# phy0.net
KiCad netlist of a schematic drawn in Altium Designer
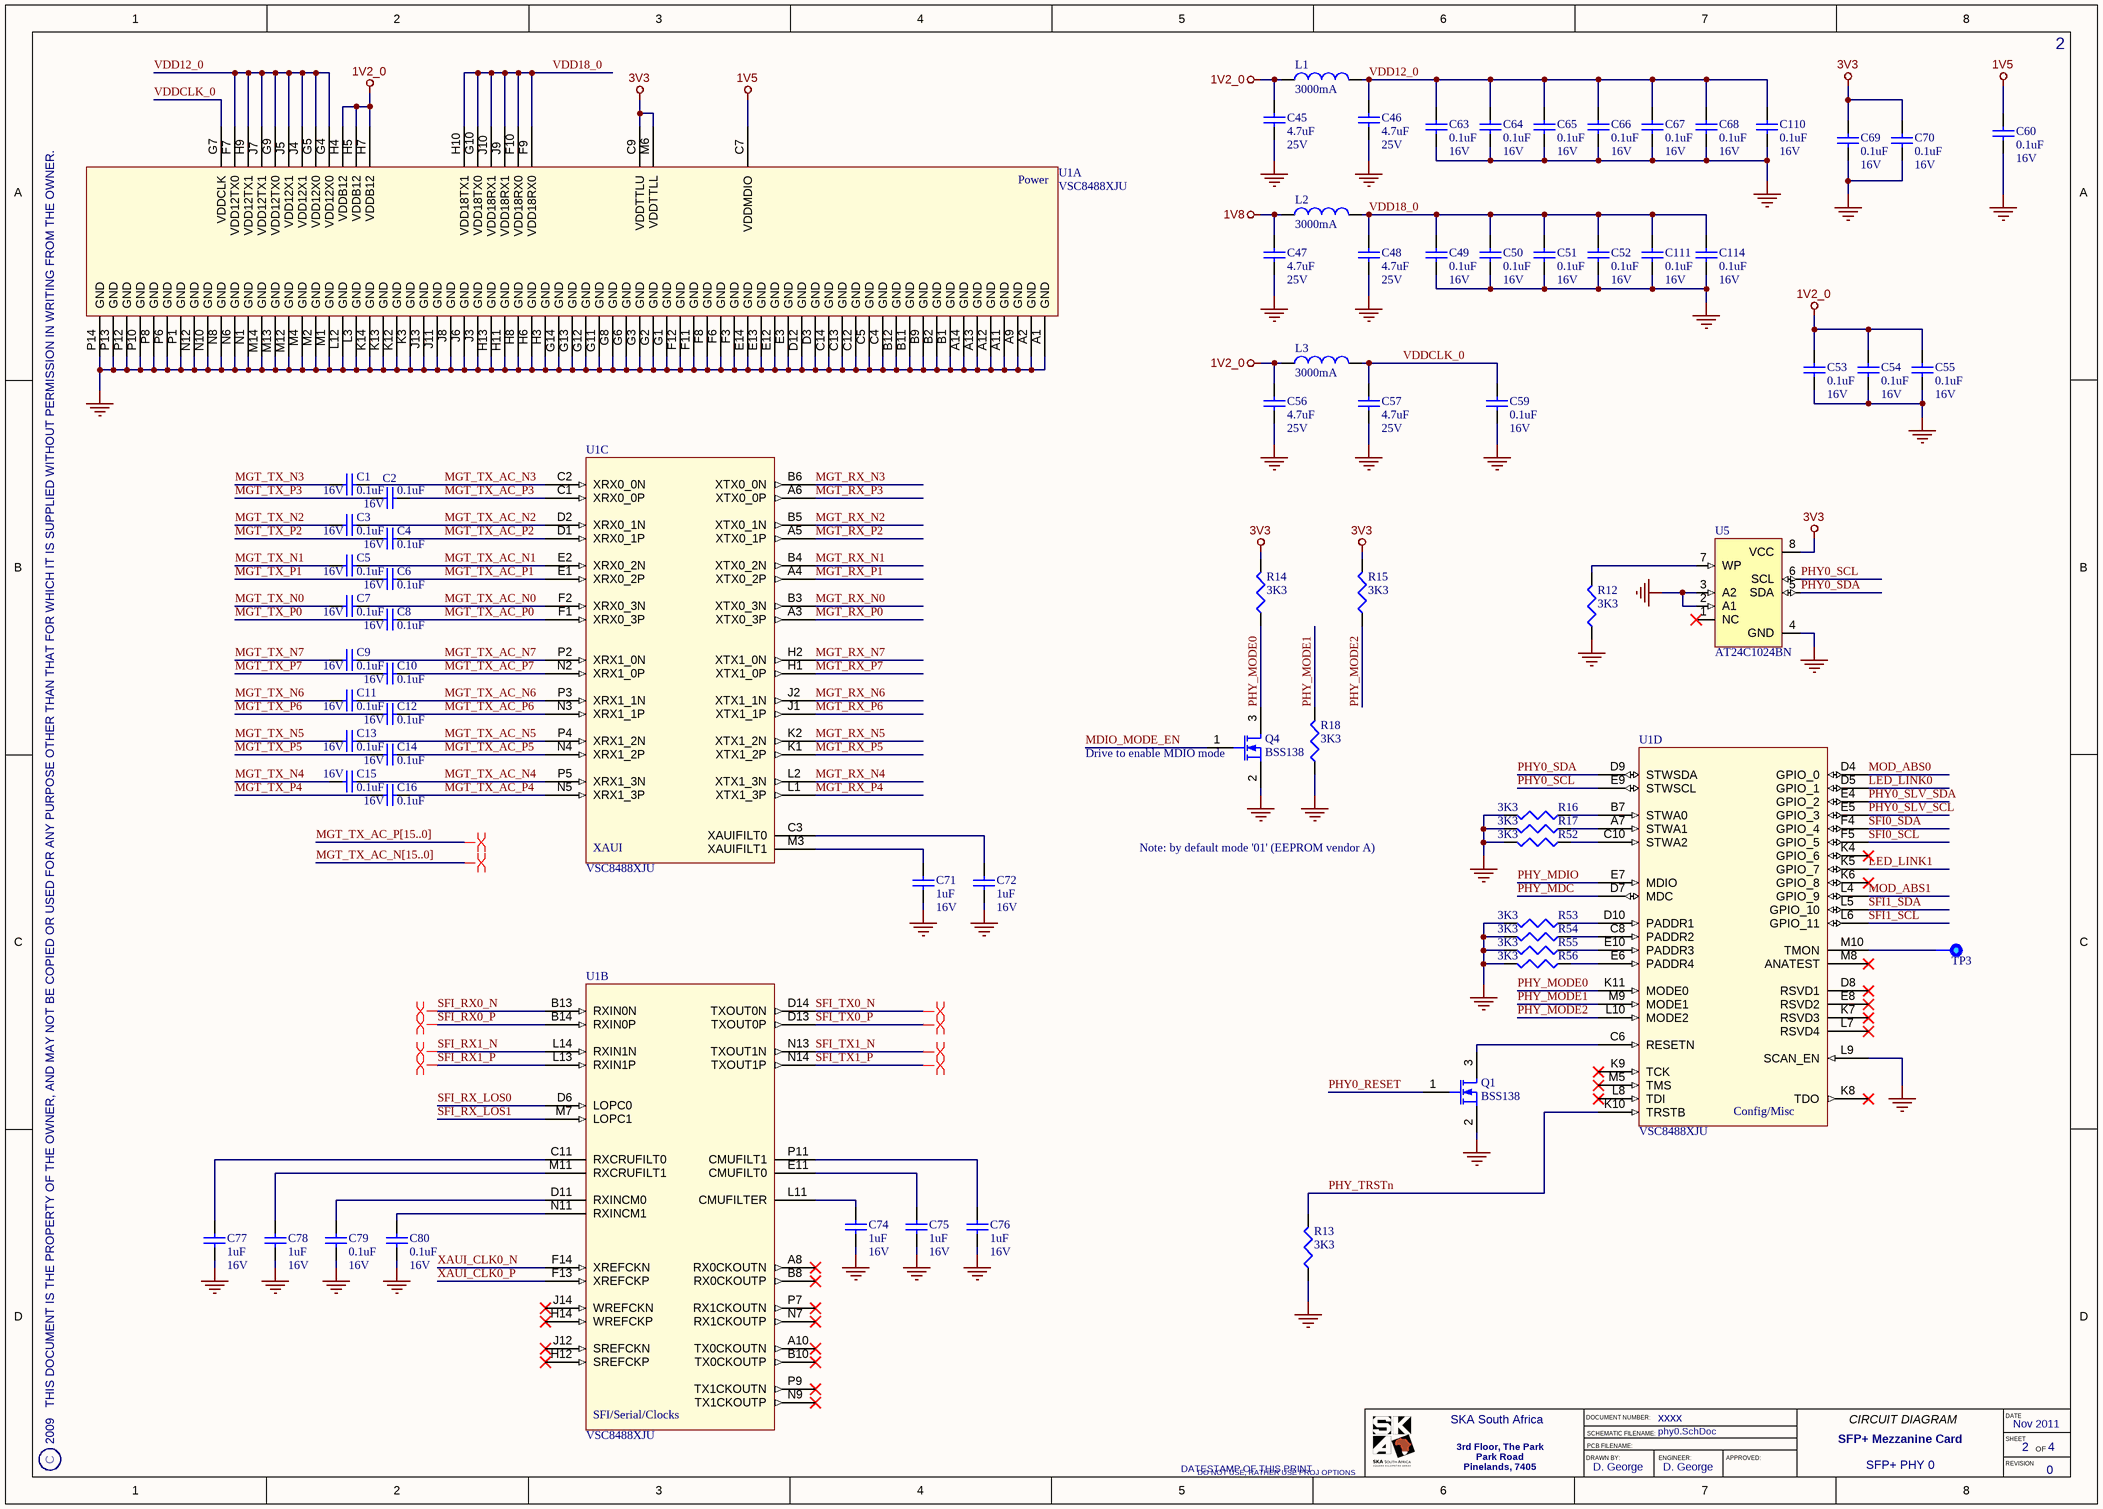
[diagram p0: phy0.SchDoc]

(export (version "E")
  (design (tool "Eeschema 10.0.6"))
  (components
    (comp (ref "C1")
      (value "0.1uF")
      (footprint "CAPC1005X60L")
      (description "0.1uF, Ceramic Capacitor")
      (fields
        (field (name "RATING") "16V")
        (field (name "MANUFACTURER") "VENKEL")
        (field (name "PARTNUM") "C0402X7R160-104KN")
      )
      (libsource (lib "altium_db") (part "CapStd"))
    )
    (comp (ref "C2")
      (value "0.1uF")
      (footprint "CAPC1005X60L")
      (description "0.1uF, Ceramic Capacitor")
      (fields
        (field (name "RATING") "16V")
        (field (name "MANUFACTURER") "VENKEL")
        (field (name "PARTNUM") "C0402X7R160-104KN")
      )
      (libsource (lib "altium_db") (part "CapStd"))
    )
    (comp (ref "C3")
      (value "0.1uF")
      (footprint "CAPC1005X60L")
      (description "0.1uF, Ceramic Capacitor")
      (fields
        (field (name "RATING") "16V")
        (field (name "MANUFACTURER") "VENKEL")
        (field (name "PARTNUM") "C0402X7R160-104KN")
      )
      (libsource (lib "altium_db") (part "CapStd"))
    )
    (comp (ref "C4")
      (value "0.1uF")
      (footprint "CAPC1005X60L")
      (description "0.1uF, Ceramic Capacitor")
      (fields
        (field (name "RATING") "16V")
        (field (name "MANUFACTURER") "VENKEL")
        (field (name "PARTNUM") "C0402X7R160-104KN")
      )
      (libsource (lib "altium_db") (part "CapStd"))
    )
    (comp (ref "C5")
      (value "0.1uF")
      (footprint "CAPC1005X60L")
      (description "0.1uF, Ceramic Capacitor")
      (fields
        (field (name "RATING") "16V")
        (field (name "MANUFACTURER") "VENKEL")
        (field (name "PARTNUM") "C0402X7R160-104KN")
      )
      (libsource (lib "altium_db") (part "CapStd"))
    )
    (comp (ref "C6")
      (value "0.1uF")
      (footprint "CAPC1005X60L")
      (description "0.1uF, Ceramic Capacitor")
      (fields
        (field (name "RATING") "16V")
        (field (name "MANUFACTURER") "VENKEL")
        (field (name "PARTNUM") "C0402X7R160-104KN")
      )
      (libsource (lib "altium_db") (part "CapStd"))
    )
    (comp (ref "C7")
      (value "0.1uF")
      (footprint "CAPC1005X60L")
      (description "0.1uF, Ceramic Capacitor")
      (fields
        (field (name "RATING") "16V")
        (field (name "MANUFACTURER") "VENKEL")
        (field (name "PARTNUM") "C0402X7R160-104KN")
      )
      (libsource (lib "altium_db") (part "CapStd"))
    )
    (comp (ref "C8")
      (value "0.1uF")
      (footprint "CAPC1005X60L")
      (description "0.1uF, Ceramic Capacitor")
      (fields
        (field (name "RATING") "16V")
        (field (name "MANUFACTURER") "VENKEL")
        (field (name "PARTNUM") "C0402X7R160-104KN")
      )
      (libsource (lib "altium_db") (part "CapStd"))
    )
    (comp (ref "C9")
      (value "0.1uF")
      (footprint "CAPC1005X60L")
      (description "0.1uF, Ceramic Capacitor")
      (fields
        (field (name "RATING") "16V")
        (field (name "MANUFACTURER") "VENKEL")
        (field (name "PARTNUM") "C0402X7R160-104KN")
      )
      (libsource (lib "altium_db") (part "CapStd"))
    )
    (comp (ref "C10")
      (value "0.1uF")
      (footprint "CAPC1005X60L")
      (description "0.1uF, Ceramic Capacitor")
      (fields
        (field (name "RATING") "16V")
        (field (name "MANUFACTURER") "VENKEL")
        (field (name "PARTNUM") "C0402X7R160-104KN")
      )
      (libsource (lib "altium_db") (part "CapStd"))
    )
    (comp (ref "C11")
      (value "0.1uF")
      (footprint "CAPC1005X60L")
      (description "0.1uF, Ceramic Capacitor")
      (fields
        (field (name "RATING") "16V")
        (field (name "MANUFACTURER") "VENKEL")
        (field (name "PARTNUM") "C0402X7R160-104KN")
      )
      (libsource (lib "altium_db") (part "CapStd"))
    )
    (comp (ref "C12")
      (value "0.1uF")
      (footprint "CAPC1005X60L")
      (description "0.1uF, Ceramic Capacitor")
      (fields
        (field (name "RATING") "16V")
        (field (name "MANUFACTURER") "VENKEL")
        (field (name "PARTNUM") "C0402X7R160-104KN")
      )
      (libsource (lib "altium_db") (part "CapStd"))
    )
    (comp (ref "C13")
      (value "0.1uF")
      (footprint "CAPC1005X60L")
      (description "0.1uF, Ceramic Capacitor")
      (fields
        (field (name "RATING") "16V")
        (field (name "MANUFACTURER") "VENKEL")
        (field (name "PARTNUM") "C0402X7R160-104KN")
      )
      (libsource (lib "altium_db") (part "CapStd"))
    )
    (comp (ref "C14")
      (value "0.1uF")
      (footprint "CAPC1005X60L")
      (description "0.1uF, Ceramic Capacitor")
      (fields
        (field (name "RATING") "16V")
        (field (name "MANUFACTURER") "VENKEL")
        (field (name "PARTNUM") "C0402X7R160-104KN")
      )
      (libsource (lib "altium_db") (part "CapStd"))
    )
    (comp (ref "C15")
      (value "0.1uF")
      (footprint "CAPC1005X60L")
      (description "0.1uF, Ceramic Capacitor")
      (fields
        (field (name "RATING") "16V")
        (field (name "MANUFACTURER") "VENKEL")
        (field (name "PARTNUM") "C0402X7R160-104KN")
      )
      (libsource (lib "altium_db") (part "CapStd"))
    )
    (comp (ref "C16")
      (value "0.1uF")
      (footprint "CAPC1005X60L")
      (description "0.1uF, Ceramic Capacitor")
      (fields
        (field (name "RATING") "16V")
        (field (name "MANUFACTURER") "VENKEL")
        (field (name "PARTNUM") "C0402X7R160-104KN")
      )
      (libsource (lib "altium_db") (part "CapStd"))
    )
    (comp (ref "C45")
      (value "4.7uF")
      (footprint "CAPC2012X127L")
      (description "4.7uF, Ceramic Capacitor")
      (fields
        (field (name "RATING") "25V")
        (field (name "MANUFACTURER") "MURATA")
        (field (name "PARTNUM") "GRM21BR61E475KA12K")
      )
      (libsource (lib "altium_db") (part "CapStd"))
    )
    (comp (ref "C46")
      (value "4.7uF")
      (footprint "CAPC2012X127L")
      (description "4.7uF, Ceramic Capacitor")
      (fields
        (field (name "RATING") "25V")
        (field (name "MANUFACTURER") "MURATA")
        (field (name "PARTNUM") "GRM21BR61E475KA12K")
      )
      (libsource (lib "altium_db") (part "CapStd"))
    )
    (comp (ref "C47")
      (value "4.7uF")
      (footprint "CAPC2012X127L")
      (description "4.7uF, Ceramic Capacitor")
      (fields
        (field (name "RATING") "25V")
        (field (name "MANUFACTURER") "MURATA")
        (field (name "PARTNUM") "GRM21BR61E475KA12K")
      )
      (libsource (lib "altium_db") (part "CapStd"))
    )
    (comp (ref "C48")
      (value "4.7uF")
      (footprint "CAPC2012X127L")
      (description "4.7uF, Ceramic Capacitor")
      (fields
        (field (name "RATING") "25V")
        (field (name "MANUFACTURER") "MURATA")
        (field (name "PARTNUM") "GRM21BR61E475KA12K")
      )
      (libsource (lib "altium_db") (part "CapStd"))
    )
    (comp (ref "C49")
      (value "0.1uF")
      (footprint "CAPC1005X60L")
      (description "0.1uF, Ceramic Capacitor")
      (fields
        (field (name "RATING") "16V")
        (field (name "MANUFACTURER") "VENKEL")
        (field (name "PARTNUM") "C0402X7R160-104KN")
      )
      (libsource (lib "altium_db") (part "CapStd"))
    )
    (comp (ref "C50")
      (value "0.1uF")
      (footprint "CAPC1005X60L")
      (description "0.1uF, Ceramic Capacitor")
      (fields
        (field (name "RATING") "16V")
        (field (name "MANUFACTURER") "VENKEL")
        (field (name "PARTNUM") "C0402X7R160-104KN")
      )
      (libsource (lib "altium_db") (part "CapStd"))
    )
    (comp (ref "C51")
      (value "0.1uF")
      (footprint "CAPC1005X60L")
      (description "0.1uF, Ceramic Capacitor")
      (fields
        (field (name "RATING") "16V")
        (field (name "MANUFACTURER") "VENKEL")
        (field (name "PARTNUM") "C0402X7R160-104KN")
      )
      (libsource (lib "altium_db") (part "CapStd"))
    )
    (comp (ref "C52")
      (value "0.1uF")
      (footprint "CAPC1005X60L")
      (description "0.1uF, Ceramic Capacitor")
      (fields
        (field (name "RATING") "16V")
        (field (name "MANUFACTURER") "VENKEL")
        (field (name "PARTNUM") "C0402X7R160-104KN")
      )
      (libsource (lib "altium_db") (part "CapStd"))
    )
    (comp (ref "C53")
      (value "0.1uF")
      (footprint "CAPC1005X60L")
      (description "0.1uF, Ceramic Capacitor")
      (fields
        (field (name "RATING") "16V")
        (field (name "MANUFACTURER") "VENKEL")
        (field (name "PARTNUM") "C0402X7R160-104KN")
      )
      (libsource (lib "altium_db") (part "CapStd"))
    )
    (comp (ref "C54")
      (value "0.1uF")
      (footprint "CAPC1005X60L")
      (description "0.1uF, Ceramic Capacitor")
      (fields
        (field (name "RATING") "16V")
        (field (name "MANUFACTURER") "VENKEL")
        (field (name "PARTNUM") "C0402X7R160-104KN")
      )
      (libsource (lib "altium_db") (part "CapStd"))
    )
    (comp (ref "C55")
      (value "0.1uF")
      (footprint "CAPC1005X60L")
      (description "0.1uF, Ceramic Capacitor")
      (fields
        (field (name "RATING") "16V")
        (field (name "MANUFACTURER") "VENKEL")
        (field (name "PARTNUM") "C0402X7R160-104KN")
      )
      (libsource (lib "altium_db") (part "CapStd"))
    )
    (comp (ref "C56")
      (value "4.7uF")
      (footprint "CAPC2012X127L")
      (description "4.7uF, Ceramic Capacitor")
      (fields
        (field (name "RATING") "25V")
        (field (name "MANUFACTURER") "MURATA")
        (field (name "PARTNUM") "GRM21BR61E475KA12K")
      )
      (libsource (lib "altium_db") (part "CapStd"))
    )
    (comp (ref "C57")
      (value "4.7uF")
      (footprint "CAPC2012X127L")
      (description "4.7uF, Ceramic Capacitor")
      (fields
        (field (name "RATING") "25V")
        (field (name "MANUFACTURER") "MURATA")
        (field (name "PARTNUM") "GRM21BR61E475KA12K")
      )
      (libsource (lib "altium_db") (part "CapStd"))
    )
    (comp (ref "C59")
      (value "0.1uF")
      (footprint "CAPC1005X60L")
      (description "0.1uF, Ceramic Capacitor")
      (fields
        (field (name "RATING") "16V")
        (field (name "MANUFACTURER") "VENKEL")
        (field (name "PARTNUM") "C0402X7R160-104KN")
      )
      (libsource (lib "altium_db") (part "CapStd"))
    )
    (comp (ref "C60")
      (value "0.1uF")
      (footprint "CAPC1005X60L")
      (description "0.1uF, Ceramic Capacitor")
      (fields
        (field (name "RATING") "16V")
        (field (name "MANUFACTURER") "VENKEL")
        (field (name "PARTNUM") "C0402X7R160-104KN")
      )
      (libsource (lib "altium_db") (part "CapStd"))
    )
    (comp (ref "C63")
      (value "0.1uF")
      (footprint "CAPC1005X60L")
      (description "0.1uF, Ceramic Capacitor")
      (fields
        (field (name "RATING") "16V")
        (field (name "MANUFACTURER") "VENKEL")
        (field (name "PARTNUM") "C0402X7R160-104KN")
      )
      (libsource (lib "altium_db") (part "CapStd"))
    )
    (comp (ref "C64")
      (value "0.1uF")
      (footprint "CAPC1005X60L")
      (description "0.1uF, Ceramic Capacitor")
      (fields
        (field (name "RATING") "16V")
        (field (name "MANUFACTURER") "VENKEL")
        (field (name "PARTNUM") "C0402X7R160-104KN")
      )
      (libsource (lib "altium_db") (part "CapStd"))
    )
    (comp (ref "C65")
      (value "0.1uF")
      (footprint "CAPC1005X60L")
      (description "0.1uF, Ceramic Capacitor")
      (fields
        (field (name "RATING") "16V")
        (field (name "MANUFACTURER") "VENKEL")
        (field (name "PARTNUM") "C0402X7R160-104KN")
      )
      (libsource (lib "altium_db") (part "CapStd"))
    )
    (comp (ref "C66")
      (value "0.1uF")
      (footprint "CAPC1005X60L")
      (description "0.1uF, Ceramic Capacitor")
      (fields
        (field (name "RATING") "16V")
        (field (name "MANUFACTURER") "VENKEL")
        (field (name "PARTNUM") "C0402X7R160-104KN")
      )
      (libsource (lib "altium_db") (part "CapStd"))
    )
    (comp (ref "C67")
      (value "0.1uF")
      (footprint "CAPC1005X60L")
      (description "0.1uF, Ceramic Capacitor")
      (fields
        (field (name "RATING") "16V")
        (field (name "MANUFACTURER") "VENKEL")
        (field (name "PARTNUM") "C0402X7R160-104KN")
      )
      (libsource (lib "altium_db") (part "CapStd"))
    )
    (comp (ref "C68")
      (value "0.1uF")
      (footprint "CAPC1005X60L")
      (description "0.1uF, Ceramic Capacitor")
      (fields
        (field (name "RATING") "16V")
        (field (name "MANUFACTURER") "VENKEL")
        (field (name "PARTNUM") "C0402X7R160-104KN")
      )
      (libsource (lib "altium_db") (part "CapStd"))
    )
    (comp (ref "C69")
      (value "0.1uF")
      (footprint "CAPC1005X60L")
      (description "0.1uF, Ceramic Capacitor")
      (fields
        (field (name "RATING") "16V")
        (field (name "MANUFACTURER") "VENKEL")
        (field (name "PARTNUM") "C0402X7R160-104KN")
      )
      (libsource (lib "altium_db") (part "CapStd"))
    )
    (comp (ref "C70")
      (value "0.1uF")
      (footprint "CAPC1005X60L")
      (description "0.1uF, Ceramic Capacitor")
      (fields
        (field (name "RATING") "16V")
        (field (name "MANUFACTURER") "VENKEL")
        (field (name "PARTNUM") "C0402X7R160-104KN")
      )
      (libsource (lib "altium_db") (part "CapStd"))
    )
    (comp (ref "C71")
      (value "1uF")
      (footprint "CAPC2012X127L")
      (description "1uF, Ceramic Capacitor")
      (fields
        (field (name "RATING") "16V")
        (field (name "MANUFACTURER") "MURATA")
        (field (name "PARTNUM") "GRM21BR61C105KA01L")
      )
      (libsource (lib "altium_db") (part "CapStd"))
    )
    (comp (ref "C72")
      (value "1uF")
      (footprint "CAPC2012X127L")
      (description "1uF, Ceramic Capacitor")
      (fields
        (field (name "RATING") "16V")
        (field (name "MANUFACTURER") "MURATA")
        (field (name "PARTNUM") "GRM21BR61C105KA01L")
      )
      (libsource (lib "altium_db") (part "CapStd"))
    )
    (comp (ref "C74")
      (value "1uF")
      (footprint "CAPC2012X127L")
      (description "1uF, Ceramic Capacitor")
      (fields
        (field (name "RATING") "16V")
        (field (name "MANUFACTURER") "MURATA")
        (field (name "PARTNUM") "GRM21BR61C105KA01L")
      )
      (libsource (lib "altium_db") (part "CapStd"))
    )
    (comp (ref "C75")
      (value "1uF")
      (footprint "CAPC2012X127L")
      (description "1uF, Ceramic Capacitor")
      (fields
        (field (name "RATING") "16V")
        (field (name "MANUFACTURER") "MURATA")
        (field (name "PARTNUM") "GRM21BR61C105KA01L")
      )
      (libsource (lib "altium_db") (part "CapStd"))
    )
    (comp (ref "C76")
      (value "1uF")
      (footprint "CAPC2012X127L")
      (description "1uF, Ceramic Capacitor")
      (fields
        (field (name "RATING") "16V")
        (field (name "MANUFACTURER") "MURATA")
        (field (name "PARTNUM") "GRM21BR61C105KA01L")
      )
      (libsource (lib "altium_db") (part "CapStd"))
    )
    (comp (ref "C77")
      (value "1uF")
      (footprint "CAPC2012X127L")
      (description "1uF, Ceramic Capacitor")
      (fields
        (field (name "RATING") "16V")
        (field (name "MANUFACTURER") "MURATA")
        (field (name "PARTNUM") "GRM21BR61C105KA01L")
      )
      (libsource (lib "altium_db") (part "CapStd"))
    )
    (comp (ref "C78")
      (value "1uF")
      (footprint "CAPC2012X127L")
      (description "1uF, Ceramic Capacitor")
      (fields
        (field (name "RATING") "16V")
        (field (name "MANUFACTURER") "MURATA")
        (field (name "PARTNUM") "GRM21BR61C105KA01L")
      )
      (libsource (lib "altium_db") (part "CapStd"))
    )
    (comp (ref "C79")
      (value "0.1uF")
      (footprint "CAPC1005X60L")
      (description "0.1uF, Ceramic Capacitor")
      (fields
        (field (name "RATING") "16V")
        (field (name "MANUFACTURER") "VENKEL")
        (field (name "PARTNUM") "C0402X7R160-104KN")
      )
      (libsource (lib "altium_db") (part "CapStd"))
    )
    (comp (ref "C80")
      (value "0.1uF")
      (footprint "CAPC1005X60L")
      (description "0.1uF, Ceramic Capacitor")
      (fields
        (field (name "RATING") "16V")
        (field (name "MANUFACTURER") "VENKEL")
        (field (name "PARTNUM") "C0402X7R160-104KN")
      )
      (libsource (lib "altium_db") (part "CapStd"))
    )
    (comp (ref "C110")
      (value "0.1uF")
      (footprint "CAPC1005X60L")
      (description "0.1uF, Ceramic Capacitor")
      (fields
        (field (name "RATING") "16V")
        (field (name "MANUFACTURER") "VENKEL")
        (field (name "PARTNUM") "C0402X7R160-104KN")
      )
      (libsource (lib "altium_db") (part "CapStd"))
    )
    (comp (ref "C111")
      (value "0.1uF")
      (footprint "CAPC1005X60L")
      (description "0.1uF, Ceramic Capacitor")
      (fields
        (field (name "RATING") "16V")
        (field (name "MANUFACTURER") "VENKEL")
        (field (name "PARTNUM") "C0402X7R160-104KN")
      )
      (libsource (lib "altium_db") (part "CapStd"))
    )
    (comp (ref "C114")
      (value "0.1uF")
      (footprint "CAPC1005X60L")
      (description "0.1uF, Ceramic Capacitor")
      (fields
        (field (name "RATING") "16V")
        (field (name "MANUFACTURER") "VENKEL")
        (field (name "PARTNUM") "C0402X7R160-104KN")
      )
      (libsource (lib "altium_db") (part "CapStd"))
    )
    (comp (ref "L1")
      (value "120R")
      (footprint "INDC3216X130L")
      (description "120 Ohm, Chip Ferrite Brad")
      (fields
        (field (name "RATING") "3000mA")
        (field (name "MANUFACTURER") "Murata")
        (field (name "PARTNUM") "BLM31PG121SN1")
      )
      (libsource (lib "altium_db") (part "IndStd"))
    )
    (comp (ref "L2")
      (value "120R")
      (footprint "INDC3216X130L")
      (description "120 Ohm, Chip Ferrite Brad")
      (fields
        (field (name "RATING") "3000mA")
        (field (name "MANUFACTURER") "Murata")
        (field (name "PARTNUM") "BLM31PG121SN1")
      )
      (libsource (lib "altium_db") (part "IndStd"))
    )
    (comp (ref "L3")
      (value "120R")
      (footprint "INDC3216X130L")
      (description "120 Ohm, Chip Ferrite Brad")
      (fields
        (field (name "RATING") "3000mA")
        (field (name "MANUFACTURER") "Murata")
        (field (name "PARTNUM") "BLM31PG121SN1")
      )
      (libsource (lib "altium_db") (part "IndStd"))
    )
    (comp (ref "Q1")
      (value "BSS138")
      (footprint "SOT95P245X110-3N")
      (description "N-Channel Logic Level Enhancement Mode Field Effect Transistor")
      (fields (field (name "MANUFACTURER") "Fairchild Semiconductor"))
      (libsource (lib "altium_db") (part "BSS138"))
    )
    (comp (ref "Q4")
      (value "BSS138")
      (footprint "SOT95P245X110-3N")
      (description "N-Channel Logic Level Enhancement Mode Field Effect Transistor")
      (fields (field (name "MANUFACTURER") "Fairchild Semiconductor"))
      (libsource (lib "altium_db") (part "BSS138"))
    )
    (comp (ref "R12")
      (value "3K3")
      (footprint "RESC1005X40L")
      (description "3K3, 1.1mm x 0.5mm, Thick Film Resistor")
      (fields (field (name "MANUFACTURER") "ROYALOHM") (field (name "PARTNUM") "0402WGJ0332T1E"))
      (libsource (lib "altium_db") (part "ResStd"))
    )
    (comp (ref "R13")
      (value "3K3")
      (footprint "RESC1005X40L")
      (description "3K3, 1.1mm x 0.5mm, Thick Film Resistor")
      (fields (field (name "MANUFACTURER") "ROYALOHM") (field (name "PARTNUM") "0402WGJ0332T1E"))
      (libsource (lib "altium_db") (part "ResStd"))
    )
    (comp (ref "R14")
      (value "3K3")
      (footprint "RESC1005X40L")
      (description "3K3, 1.1mm x 0.5mm, Thick Film Resistor")
      (fields (field (name "MANUFACTURER") "ROYALOHM") (field (name "PARTNUM") "0402WGJ0332T1E"))
      (libsource (lib "altium_db") (part "ResStd"))
    )
    (comp (ref "R15")
      (value "3K3")
      (footprint "RESC1005X40L")
      (description "3K3, 1.1mm x 0.5mm, Thick Film Resistor")
      (fields (field (name "MANUFACTURER") "ROYALOHM") (field (name "PARTNUM") "0402WGJ0332T1E"))
      (libsource (lib "altium_db") (part "ResStd"))
    )
    (comp (ref "R16")
      (value "3K3")
      (footprint "RESC1005X40L")
      (description "3K3, 1.1mm x 0.5mm, Thick Film Resistor")
      (fields (field (name "MANUFACTURER") "ROYALOHM") (field (name "PARTNUM") "0402WGJ0332T1E"))
      (libsource (lib "altium_db") (part "ResStd"))
    )
    (comp (ref "R17")
      (value "3K3")
      (footprint "RESC1005X40L")
      (description "3K3, 1.1mm x 0.5mm, Thick Film Resistor")
      (fields (field (name "MANUFACTURER") "ROYALOHM") (field (name "PARTNUM") "0402WGJ0332T1E"))
      (libsource (lib "altium_db") (part "ResStd"))
    )
    (comp (ref "R18")
      (value "3K3")
      (footprint "RESC1005X40L")
      (description "3K3, 1.1mm x 0.5mm, Thick Film Resistor")
      (fields (field (name "MANUFACTURER") "ROYALOHM") (field (name "PARTNUM") "0402WGJ0332T1E"))
      (libsource (lib "altium_db") (part "ResStd"))
    )
    (comp (ref "R52")
      (value "3K3")
      (footprint "RESC1005X40L")
      (description "3K3, 1.1mm x 0.5mm, Thick Film Resistor")
      (fields (field (name "MANUFACTURER") "ROYALOHM") (field (name "PARTNUM") "0402WGJ0332T1E"))
      (libsource (lib "altium_db") (part "ResStd"))
    )
    (comp (ref "R53")
      (value "3K3")
      (footprint "RESC1005X40L")
      (description "3K3, 1.1mm x 0.5mm, Thick Film Resistor")
      (fields (field (name "MANUFACTURER") "ROYALOHM") (field (name "PARTNUM") "0402WGJ0332T1E"))
      (libsource (lib "altium_db") (part "ResStd"))
    )
    (comp (ref "R54")
      (value "3K3")
      (footprint "RESC1005X40L")
      (description "3K3, 1.1mm x 0.5mm, Thick Film Resistor")
      (fields (field (name "MANUFACTURER") "ROYALOHM") (field (name "PARTNUM") "0402WGJ0332T1E"))
      (libsource (lib "altium_db") (part "ResStd"))
    )
    (comp (ref "R55")
      (value "3K3")
      (footprint "RESC1005X40L")
      (description "3K3, 1.1mm x 0.5mm, Thick Film Resistor")
      (fields (field (name "MANUFACTURER") "ROYALOHM") (field (name "PARTNUM") "0402WGJ0332T1E"))
      (libsource (lib "altium_db") (part "ResStd"))
    )
    (comp (ref "R56")
      (value "3K3")
      (footprint "RESC1005X40L")
      (description "3K3, 1.1mm x 0.5mm, Thick Film Resistor")
      (fields (field (name "MANUFACTURER") "ROYALOHM") (field (name "PARTNUM") "0402WGJ0332T1E"))
      (libsource (lib "altium_db") (part "ResStd"))
    )
    (comp (ref "TP3")
      (value "Testpoint")
      (footprint "TP100")
      (description "1mm Diameter, through-hole, Circular Test-point")
      (libsource (lib "altium_db") (part "Testpoint"))
    )
    (comp (ref "U1")
      (value "VSC8488XJU")
      (footprint "BGA196C100P14X14_1500x1500x140")
      (description "DualChannel WAN/LAN/Backplane XAUI to SFP+/KR Transceiver")
      (fields (field (name "MANUFACTURER") "Vitesse"))
      (libsource (lib "altium_db") (part "VSC8488XJU"))
    )
    (comp (ref "U5")
      (value "AT24C1024BN")
      (footprint "SOIC150-8_N")
      (description "1M, SOIC-8, Serial EEPROM")
      (fields (field (name "MANUFACTURER") "Atmel") (field (name "PARTNUM") "AT24C1024BN-SH-B"))
      (libsource (lib "altium_db") (part "AT24C1024BN-SH"))
    )
  )
  (nets
    (net (code "17") (name "/LED_LINK0") (class "Default")
      (node (ref "U1") (pin "D5") (pinfunction "GPIO_1_D5") (pintype "bidirectional"))
    )
    (net (code "18") (name "/LED_LINK1") (class "Default")
      (node (ref "U1") (pin "K5") (pinfunction "GPIO_7_K5") (pintype "bidirectional"))
    )
    (net (code "19") (name "/MDIO_MODE_EN") (class "Default")
      (node (ref "Q4") (pin "1") (pinfunction "G_1") (pintype "passive"))
    )
    (net (code "20") (name "/MGT_RX_N0") (class "Default")
      (node (ref "U1") (pin "B3") (pinfunction "XTX0_3N_B3") (pintype "output"))
    )
    (net (code "21") (name "/MGT_RX_N1") (class "Default")
      (node (ref "U1") (pin "B4") (pinfunction "XTX0_2N_B4") (pintype "output"))
    )
    (net (code "22") (name "/MGT_RX_N2") (class "Default")
      (node (ref "U1") (pin "B5") (pinfunction "XTX0_1N_B5") (pintype "output"))
    )
    (net (code "23") (name "/MGT_RX_N3") (class "Default")
      (node (ref "U1") (pin "B6") (pinfunction "XTX0_0N_B6") (pintype "output"))
    )
    (net (code "24") (name "/MGT_RX_N4") (class "Default")
      (node (ref "U1") (pin "L2") (pinfunction "XTX1_3N_L2") (pintype "output"))
    )
    (net (code "25") (name "/MGT_RX_N5") (class "Default")
      (node (ref "U1") (pin "K2") (pinfunction "XTX1_2N_K2") (pintype "output"))
    )
    (net (code "26") (name "/MGT_RX_N6") (class "Default")
      (node (ref "U1") (pin "J2") (pinfunction "XTX1_1N_J2") (pintype "output"))
    )
    (net (code "27") (name "/MGT_RX_N7") (class "Default")
      (node (ref "U1") (pin "H2") (pinfunction "XTX1_0N_H2") (pintype "output"))
    )
    (net (code "28") (name "/MGT_RX_P0") (class "Default")
      (node (ref "U1") (pin "A3") (pinfunction "XTX0_3P_A3") (pintype "output"))
    )
    (net (code "29") (name "/MGT_RX_P1") (class "Default")
      (node (ref "U1") (pin "A4") (pinfunction "XTX0_2P_A4") (pintype "output"))
    )
    (net (code "30") (name "/MGT_RX_P2") (class "Default")
      (node (ref "U1") (pin "A5") (pinfunction "XTX0_1P_A5") (pintype "output"))
    )
    (net (code "31") (name "/MGT_RX_P3") (class "Default")
      (node (ref "U1") (pin "A6") (pinfunction "XTX0_0P_A6") (pintype "output"))
    )
    (net (code "32") (name "/MGT_RX_P4") (class "Default")
      (node (ref "U1") (pin "L1") (pinfunction "XTX1_3P_L1") (pintype "output"))
    )
    (net (code "33") (name "/MGT_RX_P5") (class "Default")
      (node (ref "U1") (pin "K1") (pinfunction "XTX1_2P_K1") (pintype "output"))
    )
    (net (code "34") (name "/MGT_RX_P6") (class "Default")
      (node (ref "U1") (pin "J1") (pinfunction "XTX1_1P_J1") (pintype "output"))
    )
    (net (code "35") (name "/MGT_RX_P7") (class "Default")
      (node (ref "U1") (pin "H1") (pinfunction "XTX1_0P_H1") (pintype "output"))
    )
    (net (code "36") (name "/MGT_TX_AC_N0") (class "Default")
      (node (ref "C7") (pin "1") (pinfunction "1_1") (pintype "passive"))
      (node (ref "U1") (pin "F2") (pinfunction "XRX0_3N_F2") (pintype "input"))
    )
    (net (code "37") (name "/MGT_TX_AC_N1") (class "Default")
      (node (ref "C5") (pin "1") (pinfunction "1_1") (pintype "passive"))
      (node (ref "U1") (pin "E2") (pinfunction "XRX0_2N_E2") (pintype "input"))
    )
    (net (code "38") (name "/MGT_TX_AC_N2") (class "Default")
      (node (ref "C3") (pin "1") (pinfunction "1_1") (pintype "passive"))
      (node (ref "U1") (pin "D2") (pinfunction "XRX0_1N_D2") (pintype "input"))
    )
    (net (code "39") (name "/MGT_TX_AC_N3") (class "Default")
      (node (ref "C1") (pin "1") (pinfunction "1_1") (pintype "passive"))
      (node (ref "U1") (pin "C2") (pinfunction "XRX0_0N_C2") (pintype "input"))
    )
    (net (code "40") (name "/MGT_TX_AC_N4") (class "Default")
      (node (ref "C15") (pin "1") (pinfunction "1_1") (pintype "passive"))
      (node (ref "U1") (pin "P5") (pinfunction "XRX1_3N_P5") (pintype "input"))
    )
    (net (code "41") (name "/MGT_TX_AC_N5") (class "Default")
      (node (ref "C13") (pin "1") (pinfunction "1_1") (pintype "passive"))
      (node (ref "U1") (pin "P4") (pinfunction "XRX1_2N_P4") (pintype "input"))
    )
    (net (code "42") (name "/MGT_TX_AC_N6") (class "Default")
      (node (ref "C11") (pin "1") (pinfunction "1_1") (pintype "passive"))
      (node (ref "U1") (pin "P3") (pinfunction "XRX1_1N_P3") (pintype "input"))
    )
    (net (code "43") (name "/MGT_TX_AC_N7") (class "Default")
      (node (ref "C9") (pin "1") (pinfunction "1_1") (pintype "passive"))
      (node (ref "U1") (pin "P2") (pinfunction "XRX1_0N_P2") (pintype "input"))
    )
    (net (code "45") (name "/MGT_TX_AC_P0") (class "Default")
      (node (ref "C8") (pin "1") (pinfunction "1_1") (pintype "passive"))
      (node (ref "U1") (pin "F1") (pinfunction "XRX0_3P_F1") (pintype "input"))
    )
    (net (code "46") (name "/MGT_TX_AC_P1") (class "Default")
      (node (ref "C6") (pin "1") (pinfunction "1_1") (pintype "passive"))
      (node (ref "U1") (pin "E1") (pinfunction "XRX0_2P_E1") (pintype "input"))
    )
    (net (code "47") (name "/MGT_TX_AC_P2") (class "Default")
      (node (ref "C4") (pin "1") (pinfunction "1_1") (pintype "passive"))
      (node (ref "U1") (pin "D1") (pinfunction "XRX0_1P_D1") (pintype "input"))
    )
    (net (code "48") (name "/MGT_TX_AC_P3") (class "Default")
      (node (ref "C2") (pin "1") (pinfunction "1_1") (pintype "passive"))
      (node (ref "U1") (pin "C1") (pinfunction "XRX0_0P_C1") (pintype "input"))
    )
    (net (code "49") (name "/MGT_TX_AC_P4") (class "Default")
      (node (ref "C16") (pin "1") (pinfunction "1_1") (pintype "passive"))
      (node (ref "U1") (pin "N5") (pinfunction "XRX1_3P_N5") (pintype "input"))
    )
    (net (code "50") (name "/MGT_TX_AC_P5") (class "Default")
      (node (ref "C14") (pin "1") (pinfunction "1_1") (pintype "passive"))
      (node (ref "U1") (pin "N4") (pinfunction "XRX1_2P_N4") (pintype "input"))
    )
    (net (code "51") (name "/MGT_TX_AC_P6") (class "Default")
      (node (ref "C12") (pin "1") (pinfunction "1_1") (pintype "passive"))
      (node (ref "U1") (pin "N3") (pinfunction "XRX1_1P_N3") (pintype "input"))
    )
    (net (code "52") (name "/MGT_TX_AC_P7") (class "Default")
      (node (ref "C10") (pin "1") (pinfunction "1_1") (pintype "passive"))
      (node (ref "U1") (pin "N2") (pinfunction "XRX1_0P_N2") (pintype "input"))
    )
    (net (code "54") (name "/MGT_TX_N0") (class "Default")
      (node (ref "C7") (pin "2") (pinfunction "2_2") (pintype "passive"))
    )
    (net (code "55") (name "/MGT_TX_N1") (class "Default")
      (node (ref "C5") (pin "2") (pinfunction "2_2") (pintype "passive"))
    )
    (net (code "56") (name "/MGT_TX_N2") (class "Default")
      (node (ref "C3") (pin "2") (pinfunction "2_2") (pintype "passive"))
    )
    (net (code "57") (name "/MGT_TX_N3") (class "Default")
      (node (ref "C1") (pin "2") (pinfunction "2_2") (pintype "passive"))
    )
    (net (code "58") (name "/MGT_TX_N4") (class "Default")
      (node (ref "C15") (pin "2") (pinfunction "2_2") (pintype "passive"))
    )
    (net (code "59") (name "/MGT_TX_N5") (class "Default")
      (node (ref "C13") (pin "2") (pinfunction "2_2") (pintype "passive"))
    )
    (net (code "60") (name "/MGT_TX_N6") (class "Default")
      (node (ref "C11") (pin "2") (pinfunction "2_2") (pintype "passive"))
    )
    (net (code "61") (name "/MGT_TX_N7") (class "Default")
      (node (ref "C9") (pin "2") (pinfunction "2_2") (pintype "passive"))
    )
    (net (code "62") (name "/MGT_TX_P0") (class "Default")
      (node (ref "C8") (pin "2") (pinfunction "2_2") (pintype "passive"))
    )
    (net (code "63") (name "/MGT_TX_P1") (class "Default")
      (node (ref "C6") (pin "2") (pinfunction "2_2") (pintype "passive"))
    )
    (net (code "64") (name "/MGT_TX_P2") (class "Default")
      (node (ref "C4") (pin "2") (pinfunction "2_2") (pintype "passive"))
    )
    (net (code "65") (name "/MGT_TX_P3") (class "Default")
      (node (ref "C2") (pin "2") (pinfunction "2_2") (pintype "passive"))
    )
    (net (code "66") (name "/MGT_TX_P4") (class "Default")
      (node (ref "C16") (pin "2") (pinfunction "2_2") (pintype "passive"))
    )
    (net (code "67") (name "/MGT_TX_P5") (class "Default")
      (node (ref "C14") (pin "2") (pinfunction "2_2") (pintype "passive"))
    )
    (net (code "68") (name "/MGT_TX_P6") (class "Default")
      (node (ref "C12") (pin "2") (pinfunction "2_2") (pintype "passive"))
    )
    (net (code "69") (name "/MGT_TX_P7") (class "Default")
      (node (ref "C10") (pin "2") (pinfunction "2_2") (pintype "passive"))
    )
    (net (code "70") (name "/MOD_ABS0") (class "Default")
      (node (ref "U1") (pin "D4") (pinfunction "GPIO_0_D4") (pintype "bidirectional"))
    )
    (net (code "71") (name "/MOD_ABS1") (class "Default")
      (node (ref "U1") (pin "L4") (pinfunction "GPIO_9_L4") (pintype "bidirectional"))
    )
    (net (code "72") (name "/PHY0_RESET") (class "Default")
      (node (ref "Q1") (pin "1") (pinfunction "G_1") (pintype "passive"))
    )
    (net (code "73") (name "/PHY0_SCL") (class "Default")
      (node (ref "U1") (pin "E9") (pinfunction "STWSCL_E9") (pintype "bidirectional"))
      (node (ref "U5") (pin "6") (pinfunction "SCL_6") (pintype "bidirectional"))
    )
    (net (code "74") (name "/PHY0_SDA") (class "Default")
      (node (ref "U1") (pin "D9") (pinfunction "STWSDA_D9") (pintype "bidirectional"))
      (node (ref "U5") (pin "5") (pinfunction "SDA_5") (pintype "bidirectional"))
    )
    (net (code "75") (name "/PHY0_SLV_SCL") (class "Default")
      (node (ref "U1") (pin "E5") (pinfunction "GPIO_3_E5") (pintype "bidirectional"))
    )
    (net (code "76") (name "/PHY0_SLV_SDA") (class "Default")
      (node (ref "U1") (pin "E4") (pinfunction "GPIO_2_E4") (pintype "bidirectional"))
    )
    (net (code "77") (name "/PHY_MDC") (class "Default")
      (node (ref "U1") (pin "D7") (pinfunction "MDC_D7") (pintype "bidirectional"))
    )
    (net (code "78") (name "/PHY_MDIO") (class "Default")
      (node (ref "U1") (pin "E7") (pinfunction "MDIO_E7") (pintype "input"))
    )
    (net (code "79") (name "/PHY_MODE0") (class "Default")
      (node (ref "Q4") (pin "3") (pinfunction "D_3") (pintype "passive"))
      (node (ref "R14") (pin "1") (pinfunction "1_1") (pintype "passive"))
      (node (ref "U1") (pin "K11") (pinfunction "MODE0_K11") (pintype "input"))
    )
    (net (code "80") (name "/PHY_MODE1") (class "Default")
      (node (ref "R18") (pin "2") (pinfunction "2_2") (pintype "passive"))
      (node (ref "U1") (pin "M9") (pinfunction "MODE1_M9") (pintype "input"))
    )
    (net (code "81") (name "/PHY_MODE2") (class "Default")
      (node (ref "R15") (pin "1") (pinfunction "1_1") (pintype "passive"))
      (node (ref "U1") (pin "L10") (pinfunction "MODE2_L10") (pintype "input"))
    )
    (net (code "82") (name "/PHY_TRSTn") (class "Default")
      (node (ref "R13") (pin "2") (pinfunction "2_2") (pintype "passive"))
      (node (ref "U1") (pin "K10") (pinfunction "TRSTB_K10") (pintype "input"))
    )
    (net (code "83") (name "/SFI0_SCL") (class "Default")
      (node (ref "U1") (pin "F5") (pinfunction "GPIO_5_F5") (pintype "bidirectional"))
    )
    (net (code "84") (name "/SFI0_SDA") (class "Default")
      (node (ref "U1") (pin "F4") (pinfunction "GPIO_4_F4") (pintype "bidirectional"))
    )
    (net (code "85") (name "/SFI1_SCL") (class "Default")
      (node (ref "U1") (pin "L6") (pinfunction "GPIO_11_L6") (pintype "bidirectional"))
    )
    (net (code "86") (name "/SFI1_SDA") (class "Default")
      (node (ref "U1") (pin "L5") (pinfunction "GPIO_10_L5") (pintype "bidirectional"))
    )
    (net (code "87") (name "/SFI_RX0_N") (class "Default")
      (node (ref "U1") (pin "B13") (pinfunction "RXIN0N_B13") (pintype "input"))
    )
    (net (code "88") (name "/SFI_RX0_P") (class "Default")
      (node (ref "U1") (pin "B14") (pinfunction "RXIN0P_B14") (pintype "input"))
    )
    (net (code "89") (name "/SFI_RX1_N") (class "Default")
      (node (ref "U1") (pin "L14") (pinfunction "RXIN1N_L14") (pintype "input"))
    )
    (net (code "90") (name "/SFI_RX1_P") (class "Default")
      (node (ref "U1") (pin "L13") (pinfunction "RXIN1P_L13") (pintype "input"))
    )
    (net (code "91") (name "/SFI_RX_LOS0") (class "Default")
      (node (ref "U1") (pin "D6") (pinfunction "LOPC0_D6") (pintype "input"))
    )
    (net (code "92") (name "/SFI_RX_LOS1") (class "Default")
      (node (ref "U1") (pin "M7") (pinfunction "LOPC1_M7") (pintype "input"))
    )
    (net (code "93") (name "/SFI_TX0_N") (class "Default")
      (node (ref "U1") (pin "D14") (pinfunction "TXOUT0N_D14") (pintype "output"))
    )
    (net (code "94") (name "/SFI_TX0_P") (class "Default")
      (node (ref "U1") (pin "D13") (pinfunction "TXOUT0P_D13") (pintype "output"))
    )
    (net (code "95") (name "/SFI_TX1_N") (class "Default")
      (node (ref "U1") (pin "N13") (pinfunction "TXOUT1N_N13") (pintype "output"))
    )
    (net (code "96") (name "/SFI_TX1_P") (class "Default")
      (node (ref "U1") (pin "N14") (pinfunction "TXOUT1P_N14") (pintype "output"))
    )
    (net (code "97") (name "/VDD12_0") (class "Default")
      (node (ref "C110") (pin "2") (pinfunction "2_2") (pintype "passive"))
      (node (ref "C46") (pin "2") (pinfunction "2_2") (pintype "passive"))
      (node (ref "C63") (pin "2") (pinfunction "2_2") (pintype "passive"))
      (node (ref "C64") (pin "2") (pinfunction "2_2") (pintype "passive"))
      (node (ref "C65") (pin "2") (pinfunction "2_2") (pintype "passive"))
      (node (ref "C66") (pin "2") (pinfunction "2_2") (pintype "passive"))
      (node (ref "C67") (pin "2") (pinfunction "2_2") (pintype "passive"))
      (node (ref "C68") (pin "2") (pinfunction "2_2") (pintype "passive"))
      (node (ref "L1") (pin "2") (pinfunction "2_2") (pintype "passive"))
      (node (ref "U1") (pin "F7") (pinfunction "VDD12TX0_F7") (pintype "power_in"))
      (node (ref "U1") (pin "G4") (pinfunction "VDD12X0_G4") (pintype "power_in"))
      (node (ref "U1") (pin "G5") (pinfunction "VDD12X0_G5") (pintype "power_in"))
      (node (ref "U1") (pin "G9") (pinfunction "VDD12TX0_G9") (pintype "power_in"))
      (node (ref "U1") (pin "H9") (pinfunction "VDD12TX1_H9") (pintype "power_in"))
      (node (ref "U1") (pin "J4") (pinfunction "VDD12X1_J4") (pintype "power_in"))
      (node (ref "U1") (pin "J5") (pinfunction "VDD12X1_J5") (pintype "power_in"))
      (node (ref "U1") (pin "J7") (pinfunction "VDD12TX1_J7") (pintype "power_in"))
    )
    (net (code "98") (name "/VDD18_0") (class "Default")
      (node (ref "C111") (pin "2") (pinfunction "2_2") (pintype "passive"))
      (node (ref "C114") (pin "2") (pinfunction "2_2") (pintype "passive"))
      (node (ref "C48") (pin "2") (pinfunction "2_2") (pintype "passive"))
      (node (ref "C49") (pin "2") (pinfunction "2_2") (pintype "passive"))
      (node (ref "C50") (pin "2") (pinfunction "2_2") (pintype "passive"))
      (node (ref "C51") (pin "2") (pinfunction "2_2") (pintype "passive"))
      (node (ref "C52") (pin "2") (pinfunction "2_2") (pintype "passive"))
      (node (ref "L2") (pin "2") (pinfunction "2_2") (pintype "passive"))
      (node (ref "U1") (pin "F10") (pinfunction "VDD18RX0_F10") (pintype "power_in"))
      (node (ref "U1") (pin "F9") (pinfunction "VDD18RX0_F9") (pintype "power_in"))
      (node (ref "U1") (pin "G10") (pinfunction "VDD18TX0_G10") (pintype "power_in"))
      (node (ref "U1") (pin "H10") (pinfunction "VDD18TX1_H10") (pintype "power_in"))
      (node (ref "U1") (pin "J10") (pinfunction "VDD18RX1_J10") (pintype "power_in"))
      (node (ref "U1") (pin "J9") (pinfunction "VDD18RX1_J9") (pintype "power_in"))
    )
    (net (code "99") (name "/VDDCLK_0") (class "Default")
      (node (ref "C57") (pin "2") (pinfunction "2_2") (pintype "passive"))
      (node (ref "C59") (pin "2") (pinfunction "2_2") (pintype "passive"))
      (node (ref "L3") (pin "2") (pinfunction "2_2") (pintype "passive"))
      (node (ref "U1") (pin "G7") (pinfunction "VDDCLK_G7") (pintype "power_in"))
    )
    (net (code "100") (name "/XAUI_CLK0_N") (class "Default")
      (node (ref "U1") (pin "F14") (pinfunction "XREFCKN_F14") (pintype "input"))
    )
    (net (code "101") (name "/XAUI_CLK0_P") (class "Default")
      (node (ref "U1") (pin "F13") (pinfunction "XREFCKP_F13") (pintype "input"))
    )
    (net (code "102") (name "1V2_0") (class "Default")
      (node (ref "C45") (pin "2") (pinfunction "2_2") (pintype "passive"))
      (node (ref "C53") (pin "2") (pinfunction "2_2") (pintype "passive"))
      (node (ref "C54") (pin "2") (pinfunction "2_2") (pintype "passive"))
      (node (ref "C55") (pin "2") (pinfunction "2_2") (pintype "passive"))
      (node (ref "C56") (pin "2") (pinfunction "2_2") (pintype "passive"))
      (node (ref "L1") (pin "1") (pinfunction "1_1") (pintype "passive"))
      (node (ref "L3") (pin "1") (pinfunction "1_1") (pintype "passive"))
      (node (ref "U1") (pin "H4") (pinfunction "VDDB12_H4") (pintype "power_in"))
      (node (ref "U1") (pin "H5") (pinfunction "VDDB12_H5") (pintype "power_in"))
      (node (ref "U1") (pin "H7") (pinfunction "VDDB12_H7") (pintype "power_in"))
    )
    (net (code "103") (name "1V5") (class "Default")
      (node (ref "C60") (pin "2") (pinfunction "2_2") (pintype "passive"))
      (node (ref "U1") (pin "C7") (pinfunction "VDDMDIO_C7") (pintype "power_in"))
    )
    (net (code "104") (name "1V8") (class "Default")
      (node (ref "C47") (pin "2") (pinfunction "2_2") (pintype "passive"))
      (node (ref "L2") (pin "1") (pinfunction "1_1") (pintype "passive"))
    )
    (net (code "105") (name "3V3") (class "Default")
      (node (ref "C69") (pin "2") (pinfunction "2_2") (pintype "passive"))
      (node (ref "C70") (pin "2") (pinfunction "2_2") (pintype "passive"))
      (node (ref "R14") (pin "2") (pinfunction "2_2") (pintype "passive"))
      (node (ref "R15") (pin "2") (pinfunction "2_2") (pintype "passive"))
      (node (ref "U1") (pin "C9") (pinfunction "VDDTTLU_C9") (pintype "power_in"))
      (node (ref "U1") (pin "M6") (pinfunction "VDDTTLL_M6") (pintype "power_in"))
      (node (ref "U5") (pin "8") (pinfunction "VCC_8") (pintype "passive"))
    )
    (net (code "106") (name "GND") (class "Default")
      (node (ref "C110") (pin "1") (pinfunction "1_1") (pintype "passive"))
      (node (ref "C111") (pin "1") (pinfunction "1_1") (pintype "passive"))
      (node (ref "C114") (pin "1") (pinfunction "1_1") (pintype "passive"))
      (node (ref "C45") (pin "1") (pinfunction "1_1") (pintype "passive"))
      (node (ref "C46") (pin "1") (pinfunction "1_1") (pintype "passive"))
      (node (ref "C47") (pin "1") (pinfunction "1_1") (pintype "passive"))
      (node (ref "C48") (pin "1") (pinfunction "1_1") (pintype "passive"))
      (node (ref "C49") (pin "1") (pinfunction "1_1") (pintype "passive"))
      (node (ref "C50") (pin "1") (pinfunction "1_1") (pintype "passive"))
      (node (ref "C51") (pin "1") (pinfunction "1_1") (pintype "passive"))
      (node (ref "C52") (pin "1") (pinfunction "1_1") (pintype "passive"))
      (node (ref "C53") (pin "1") (pinfunction "1_1") (pintype "passive"))
      (node (ref "C54") (pin "1") (pinfunction "1_1") (pintype "passive"))
      (node (ref "C55") (pin "1") (pinfunction "1_1") (pintype "passive"))
      (node (ref "C56") (pin "1") (pinfunction "1_1") (pintype "passive"))
      (node (ref "C57") (pin "1") (pinfunction "1_1") (pintype "passive"))
      (node (ref "C59") (pin "1") (pinfunction "1_1") (pintype "passive"))
      (node (ref "C60") (pin "1") (pinfunction "1_1") (pintype "passive"))
      (node (ref "C63") (pin "1") (pinfunction "1_1") (pintype "passive"))
      (node (ref "C64") (pin "1") (pinfunction "1_1") (pintype "passive"))
      (node (ref "C65") (pin "1") (pinfunction "1_1") (pintype "passive"))
      (node (ref "C66") (pin "1") (pinfunction "1_1") (pintype "passive"))
      (node (ref "C67") (pin "1") (pinfunction "1_1") (pintype "passive"))
      (node (ref "C68") (pin "1") (pinfunction "1_1") (pintype "passive"))
      (node (ref "C69") (pin "1") (pinfunction "1_1") (pintype "passive"))
      (node (ref "C70") (pin "1") (pinfunction "1_1") (pintype "passive"))
      (node (ref "C71") (pin "2") (pinfunction "2_2") (pintype "passive"))
      (node (ref "C72") (pin "2") (pinfunction "2_2") (pintype "passive"))
      (node (ref "C74") (pin "2") (pinfunction "2_2") (pintype "passive"))
      (node (ref "C75") (pin "2") (pinfunction "2_2") (pintype "passive"))
      (node (ref "C76") (pin "2") (pinfunction "2_2") (pintype "passive"))
      (node (ref "C77") (pin "2") (pinfunction "2_2") (pintype "passive"))
      (node (ref "C78") (pin "2") (pinfunction "2_2") (pintype "passive"))
      (node (ref "C79") (pin "1") (pinfunction "1_1") (pintype "passive"))
      (node (ref "C80") (pin "1") (pinfunction "1_1") (pintype "passive"))
      (node (ref "Q1") (pin "2") (pinfunction "S_2") (pintype "passive"))
      (node (ref "Q4") (pin "2") (pinfunction "S_2") (pintype "passive"))
      (node (ref "R12") (pin "1") (pinfunction "1_1") (pintype "passive"))
      (node (ref "R13") (pin "1") (pinfunction "1_1") (pintype "passive"))
      (node (ref "R16") (pin "2") (pinfunction "2_2") (pintype "passive"))
      (node (ref "R17") (pin "2") (pinfunction "2_2") (pintype "passive"))
      (node (ref "R18") (pin "1") (pinfunction "1_1") (pintype "passive"))
      (node (ref "R52") (pin "2") (pinfunction "2_2") (pintype "passive"))
      (node (ref "R53") (pin "2") (pinfunction "2_2") (pintype "passive"))
      (node (ref "R54") (pin "2") (pinfunction "2_2") (pintype "passive"))
      (node (ref "R55") (pin "2") (pinfunction "2_2") (pintype "passive"))
      (node (ref "R56") (pin "2") (pinfunction "2_2") (pintype "passive"))
      (node (ref "U1") (pin "A1") (pinfunction "GND_A1") (pintype "power_in"))
      (node (ref "U1") (pin "A11") (pinfunction "GND_A11") (pintype "power_in"))
      (node (ref "U1") (pin "A12") (pinfunction "GND_A12") (pintype "power_in"))
      (node (ref "U1") (pin "A13") (pinfunction "GND_A13") (pintype "power_in"))
      (node (ref "U1") (pin "A14") (pinfunction "GND_A14") (pintype "power_in"))
      (node (ref "U1") (pin "A2") (pinfunction "GND_A2") (pintype "power_in"))
      (node (ref "U1") (pin "A9") (pinfunction "GND_A9") (pintype "power_in"))
      (node (ref "U1") (pin "B1") (pinfunction "GND_B1") (pintype "power_in"))
      (node (ref "U1") (pin "B11") (pinfunction "GND_B11") (pintype "power_in"))
      (node (ref "U1") (pin "B12") (pinfunction "GND_B12") (pintype "power_in"))
      (node (ref "U1") (pin "B2") (pinfunction "GND_B2") (pintype "power_in"))
      (node (ref "U1") (pin "B9") (pinfunction "GND_B9") (pintype "power_in"))
      (node (ref "U1") (pin "C12") (pinfunction "GND_C12") (pintype "power_in"))
      (node (ref "U1") (pin "C13") (pinfunction "GND_C13") (pintype "power_in"))
      (node (ref "U1") (pin "C14") (pinfunction "GND_C14") (pintype "power_in"))
      (node (ref "U1") (pin "C4") (pinfunction "GND_C4") (pintype "power_in"))
      (node (ref "U1") (pin "C5") (pinfunction "GND_C5") (pintype "power_in"))
      (node (ref "U1") (pin "D12") (pinfunction "GND_D12") (pintype "power_in"))
      (node (ref "U1") (pin "D3") (pinfunction "GND_D3") (pintype "power_in"))
      (node (ref "U1") (pin "E12") (pinfunction "GND_E12") (pintype "power_in"))
      (node (ref "U1") (pin "E13") (pinfunction "GND_E13") (pintype "power_in"))
      (node (ref "U1") (pin "E14") (pinfunction "GND_E14") (pintype "power_in"))
      (node (ref "U1") (pin "E3") (pinfunction "GND_E3") (pintype "power_in"))
      (node (ref "U1") (pin "F11") (pinfunction "GND_F11") (pintype "power_in"))
      (node (ref "U1") (pin "F12") (pinfunction "GND_F12") (pintype "power_in"))
      (node (ref "U1") (pin "F3") (pinfunction "GND_F3") (pintype "power_in"))
      (node (ref "U1") (pin "F6") (pinfunction "GND_F6") (pintype "power_in"))
      (node (ref "U1") (pin "F8") (pinfunction "GND_F8") (pintype "power_in"))
      (node (ref "U1") (pin "G1") (pinfunction "GND_G1") (pintype "power_in"))
      (node (ref "U1") (pin "G11") (pinfunction "GND_G11") (pintype "power_in"))
      (node (ref "U1") (pin "G12") (pinfunction "GND_G12") (pintype "power_in"))
      (node (ref "U1") (pin "G13") (pinfunction "GND_G13") (pintype "power_in"))
      (node (ref "U1") (pin "G14") (pinfunction "GND_G14") (pintype "power_in"))
      (node (ref "U1") (pin "G2") (pinfunction "GND_G2") (pintype "power_in"))
      (node (ref "U1") (pin "G3") (pinfunction "GND_G3") (pintype "power_in"))
      (node (ref "U1") (pin "G6") (pinfunction "GND_G6") (pintype "power_in"))
      (node (ref "U1") (pin "G8") (pinfunction "GND_G8") (pintype "power_in"))
      (node (ref "U1") (pin "H11") (pinfunction "GND_H11") (pintype "power_in"))
      (node (ref "U1") (pin "H13") (pinfunction "GND_H13") (pintype "power_in"))
      (node (ref "U1") (pin "H3") (pinfunction "GND_H3") (pintype "power_in"))
      (node (ref "U1") (pin "H6") (pinfunction "GND_H6") (pintype "power_in"))
      (node (ref "U1") (pin "H8") (pinfunction "GND_H8") (pintype "power_in"))
      (node (ref "U1") (pin "J11") (pinfunction "GND_J11") (pintype "power_in"))
      (node (ref "U1") (pin "J13") (pinfunction "GND_J13") (pintype "power_in"))
      (node (ref "U1") (pin "J3") (pinfunction "GND_J3") (pintype "power_in"))
      (node (ref "U1") (pin "J6") (pinfunction "GND_J6") (pintype "power_in"))
      (node (ref "U1") (pin "J8") (pinfunction "GND_J8") (pintype "power_in"))
      (node (ref "U1") (pin "K12") (pinfunction "GND_K12") (pintype "power_in"))
      (node (ref "U1") (pin "K13") (pinfunction "GND_K13") (pintype "power_in"))
      (node (ref "U1") (pin "K14") (pinfunction "GND_K14") (pintype "power_in"))
      (node (ref "U1") (pin "K3") (pinfunction "GND_K3") (pintype "power_in"))
      (node (ref "U1") (pin "L12") (pinfunction "GND_L12") (pintype "power_in"))
      (node (ref "U1") (pin "L3") (pinfunction "GND_L3") (pintype "power_in"))
      (node (ref "U1") (pin "L9") (pinfunction "SCAN_EN_L9") (pintype "input"))
      (node (ref "U1") (pin "M1") (pinfunction "GND_M1") (pintype "power_in"))
      (node (ref "U1") (pin "M12") (pinfunction "GND_M12") (pintype "power_in"))
      (node (ref "U1") (pin "M13") (pinfunction "GND_M13") (pintype "power_in"))
      (node (ref "U1") (pin "M14") (pinfunction "GND_M14") (pintype "power_in"))
      (node (ref "U1") (pin "M2") (pinfunction "GND_M2") (pintype "power_in"))
      (node (ref "U1") (pin "M4") (pinfunction "GND_M4") (pintype "power_in"))
      (node (ref "U1") (pin "N1") (pinfunction "GND_N1") (pintype "power_in"))
      (node (ref "U1") (pin "N10") (pinfunction "GND_N10") (pintype "power_in"))
      (node (ref "U1") (pin "N12") (pinfunction "GND_N12") (pintype "power_in"))
      (node (ref "U1") (pin "N6") (pinfunction "GND_N6") (pintype "power_in"))
      (node (ref "U1") (pin "N8") (pinfunction "GND_N8") (pintype "power_in"))
      (node (ref "U1") (pin "P1") (pinfunction "GND_P1") (pintype "power_in"))
      (node (ref "U1") (pin "P10") (pinfunction "GND_P10") (pintype "power_in"))
      (node (ref "U1") (pin "P12") (pinfunction "GND_P12") (pintype "power_in"))
      (node (ref "U1") (pin "P13") (pinfunction "GND_P13") (pintype "power_in"))
      (node (ref "U1") (pin "P14") (pinfunction "GND_P14") (pintype "power_in"))
      (node (ref "U1") (pin "P6") (pinfunction "GND_P6") (pintype "power_in"))
      (node (ref "U1") (pin "P8") (pinfunction "GND_P8") (pintype "power_in"))
      (node (ref "U5") (pin "2") (pinfunction "A1_2") (pintype "input"))
      (node (ref "U5") (pin "3") (pinfunction "A2_3") (pintype "input"))
      (node (ref "U5") (pin "4") (pinfunction "GND_4") (pintype "passive"))
    )
    (net (code "107") (name "Net-(Q1-D)") (class "Default")
      (node (ref "Q1") (pin "3") (pinfunction "D_3") (pintype "passive"))
      (node (ref "U1") (pin "C6") (pinfunction "RESETN_C6") (pintype "input"))
    )
    (net (code "108") (name "Net-(U1B-CMUFILT0)") (class "Default")
      (node (ref "C75") (pin "1") (pinfunction "1_1") (pintype "passive"))
      (node (ref "U1") (pin "E11") (pinfunction "CMUFILT0_E11") (pintype "passive"))
    )
    (net (code "109") (name "Net-(U1B-CMUFILT1)") (class "Default")
      (node (ref "C76") (pin "1") (pinfunction "1_1") (pintype "passive"))
      (node (ref "U1") (pin "P11") (pinfunction "CMUFILT1_P11") (pintype "passive"))
    )
    (net (code "110") (name "Net-(U1B-CMUFILTER)") (class "Default")
      (node (ref "C74") (pin "1") (pinfunction "1_1") (pintype "passive"))
      (node (ref "U1") (pin "L11") (pinfunction "CMUFILTER_L11") (pintype "passive"))
    )
    (net (code "111") (name "Net-(U1B-RXCRUFILT0)") (class "Default")
      (node (ref "C77") (pin "1") (pinfunction "1_1") (pintype "passive"))
      (node (ref "U1") (pin "C11") (pinfunction "RXCRUFILT0_C11") (pintype "passive"))
    )
    (net (code "112") (name "Net-(U1B-RXCRUFILT1)") (class "Default")
      (node (ref "C78") (pin "1") (pinfunction "1_1") (pintype "passive"))
      (node (ref "U1") (pin "M11") (pinfunction "RXCRUFILT1_M11") (pintype "passive"))
    )
    (net (code "113") (name "Net-(U1B-RXINCM0)") (class "Default")
      (node (ref "C79") (pin "2") (pinfunction "2_2") (pintype "passive"))
      (node (ref "U1") (pin "D11") (pinfunction "RXINCM0_D11") (pintype "passive"))
    )
    (net (code "114") (name "Net-(U1B-RXINCM1)") (class "Default")
      (node (ref "C80") (pin "2") (pinfunction "2_2") (pintype "passive"))
      (node (ref "U1") (pin "N11") (pinfunction "RXINCM1_N11") (pintype "passive"))
    )
    (net (code "115") (name "Net-(U1C-XAUIFILT0)") (class "Default")
      (node (ref "C72") (pin "1") (pinfunction "1_1") (pintype "passive"))
      (node (ref "U1") (pin "C3") (pinfunction "XAUIFILT0_C3") (pintype "passive"))
    )
    (net (code "116") (name "Net-(U1C-XAUIFILT1)") (class "Default")
      (node (ref "C71") (pin "1") (pinfunction "1_1") (pintype "passive"))
      (node (ref "U1") (pin "M3") (pinfunction "XAUIFILT1_M3") (pintype "passive"))
    )
    (net (code "117") (name "Net-(U1D-PADDR1)") (class "Default")
      (node (ref "R53") (pin "1") (pinfunction "1_1") (pintype "passive"))
      (node (ref "U1") (pin "D10") (pinfunction "PADDR1_D10") (pintype "input"))
    )
    (net (code "118") (name "Net-(U1D-PADDR2)") (class "Default")
      (node (ref "R54") (pin "1") (pinfunction "1_1") (pintype "passive"))
      (node (ref "U1") (pin "C8") (pinfunction "PADDR2_C8") (pintype "input"))
    )
    (net (code "119") (name "Net-(U1D-PADDR3)") (class "Default")
      (node (ref "R55") (pin "1") (pinfunction "1_1") (pintype "passive"))
      (node (ref "U1") (pin "E10") (pinfunction "PADDR3_E10") (pintype "input"))
    )
    (net (code "120") (name "Net-(U1D-PADDR4)") (class "Default")
      (node (ref "R56") (pin "1") (pinfunction "1_1") (pintype "passive"))
      (node (ref "U1") (pin "E6") (pinfunction "PADDR4_E6") (pintype "input"))
    )
    (net (code "121") (name "Net-(U1D-STWA0)") (class "Default")
      (node (ref "R16") (pin "1") (pinfunction "1_1") (pintype "passive"))
      (node (ref "U1") (pin "B7") (pinfunction "STWA0_B7") (pintype "input"))
    )
    (net (code "122") (name "Net-(U1D-STWA1)") (class "Default")
      (node (ref "R17") (pin "1") (pinfunction "1_1") (pintype "passive"))
      (node (ref "U1") (pin "A7") (pinfunction "STWA1_A7") (pintype "input"))
    )
    (net (code "123") (name "Net-(U1D-STWA2)") (class "Default")
      (node (ref "R52") (pin "1") (pinfunction "1_1") (pintype "passive"))
      (node (ref "U1") (pin "C10") (pinfunction "STWA2_C10") (pintype "input"))
    )
    (net (code "124") (name "Net-(U1D-TMON)") (class "Default")
      (node (ref "TP3") (pin "1") (pinfunction "1_1") (pintype "passive"))
      (node (ref "U1") (pin "M10") (pinfunction "TMON_M10") (pintype "passive"))
    )
    (net (code "125") (name "Net-(U5-WP)") (class "Default")
      (node (ref "R12") (pin "2") (pinfunction "2_2") (pintype "passive"))
      (node (ref "U5") (pin "7") (pinfunction "WP_7") (pintype "input"))
    )
    (net (code "126") (name "unconnected-(U1B-RX0CKOUTN-PadA8)") (class "Default")
      (node (ref "U1") (pin "A8") (pinfunction "RX0CKOUTN_A8") (pintype "output+no_connect"))
    )
    (net (code "127") (name "unconnected-(U1B-RX0CKOUTP-PadB8)") (class "Default")
      (node (ref "U1") (pin "B8") (pinfunction "RX0CKOUTP_B8") (pintype "output+no_connect"))
    )
    (net (code "128") (name "unconnected-(U1B-RX1CKOUTN-PadP7)") (class "Default")
      (node (ref "U1") (pin "P7") (pinfunction "RX1CKOUTN_P7") (pintype "output+no_connect"))
    )
    (net (code "129") (name "unconnected-(U1B-RX1CKOUTP-PadN7)") (class "Default")
      (node (ref "U1") (pin "N7") (pinfunction "RX1CKOUTP_N7") (pintype "output+no_connect"))
    )
    (net (code "130") (name "unconnected-(U1B-SREFCKN-PadJ12)") (class "Default")
      (node (ref "U1") (pin "J12") (pinfunction "SREFCKN_J12") (pintype "input+no_connect"))
    )
    (net (code "131") (name "unconnected-(U1B-SREFCKP-PadH12)") (class "Default")
      (node (ref "U1") (pin "H12") (pinfunction "SREFCKP_H12") (pintype "input+no_connect"))
    )
    (net (code "132") (name "unconnected-(U1B-TX0CKOUTN-PadA10)") (class "Default")
      (node (ref "U1") (pin "A10") (pinfunction "TX0CKOUTN_A10") (pintype "output+no_connect"))
    )
    (net (code "133") (name "unconnected-(U1B-TX0CKOUTP-PadB10)") (class "Default")
      (node (ref "U1") (pin "B10") (pinfunction "TX0CKOUTP_B10") (pintype "output+no_connect"))
    )
    (net (code "134") (name "unconnected-(U1B-TX1CKOUTN-PadP9)") (class "Default")
      (node (ref "U1") (pin "P9") (pinfunction "TX1CKOUTN_P9") (pintype "output+no_connect"))
    )
    (net (code "135") (name "unconnected-(U1B-TX1CKOUTP-PadN9)") (class "Default")
      (node (ref "U1") (pin "N9") (pinfunction "TX1CKOUTP_N9") (pintype "output+no_connect"))
    )
    (net (code "136") (name "unconnected-(U1B-WREFCKN-PadJ14)") (class "Default")
      (node (ref "U1") (pin "J14") (pinfunction "WREFCKN_J14") (pintype "input+no_connect"))
    )
    (net (code "137") (name "unconnected-(U1B-WREFCKP-PadH14)") (class "Default")
      (node (ref "U1") (pin "H14") (pinfunction "WREFCKP_H14") (pintype "input+no_connect"))
    )
    (net (code "138") (name "unconnected-(U1D-ANATEST-PadM8)") (class "Default")
      (node (ref "U1") (pin "M8") (pinfunction "ANATEST_M8") (pintype "passive+no_connect"))
    )
    (net (code "139") (name "unconnected-(U1D-GPIO_6-PadK4)") (class "Default")
      (node (ref "U1") (pin "K4") (pinfunction "GPIO_6_K4") (pintype "bidirectional+no_connect"))
    )
    (net (code "140") (name "unconnected-(U1D-GPIO_8-PadK6)") (class "Default")
      (node (ref "U1") (pin "K6") (pinfunction "GPIO_8_K6") (pintype "bidirectional+no_connect"))
    )
    (net (code "141") (name "unconnected-(U1D-RSVD1-PadD8)") (class "Default")
      (node (ref "U1") (pin "D8") (pinfunction "RSVD1_D8") (pintype "passive+no_connect"))
    )
    (net (code "142") (name "unconnected-(U1D-RSVD2-PadE8)") (class "Default")
      (node (ref "U1") (pin "E8") (pinfunction "RSVD2_E8") (pintype "passive+no_connect"))
    )
    (net (code "143") (name "unconnected-(U1D-RSVD3-PadK7)") (class "Default")
      (node (ref "U1") (pin "K7") (pinfunction "RSVD3_K7") (pintype "passive+no_connect"))
    )
    (net (code "144") (name "unconnected-(U1D-RSVD4-PadL7)") (class "Default")
      (node (ref "U1") (pin "L7") (pinfunction "RSVD4_L7") (pintype "passive+no_connect"))
    )
    (net (code "145") (name "unconnected-(U1D-TCK-PadK9)") (class "Default")
      (node (ref "U1") (pin "K9") (pinfunction "TCK_K9") (pintype "input+no_connect"))
    )
    (net (code "146") (name "unconnected-(U1D-TDI-PadL8)") (class "Default")
      (node (ref "U1") (pin "L8") (pinfunction "TDI_L8") (pintype "input+no_connect"))
    )
    (net (code "147") (name "unconnected-(U1D-TDO-PadK8)") (class "Default")
      (node (ref "U1") (pin "K8") (pinfunction "TDO_K8") (pintype "output+no_connect"))
    )
    (net (code "148") (name "unconnected-(U1D-TMS-PadM5)") (class "Default")
      (node (ref "U1") (pin "M5") (pinfunction "TMS_M5") (pintype "input+no_connect"))
    )
    (net (code "149") (name "unconnected-(U5-NC-Pad1)") (class "Default")
      (node (ref "U5") (pin "1") (pinfunction "NC_1") (pintype "passive+no_connect"))
    )
  )
)
